# STML451RE_Buck_HSE.net
KiCad netlist of a schematic drawn in EAGLE
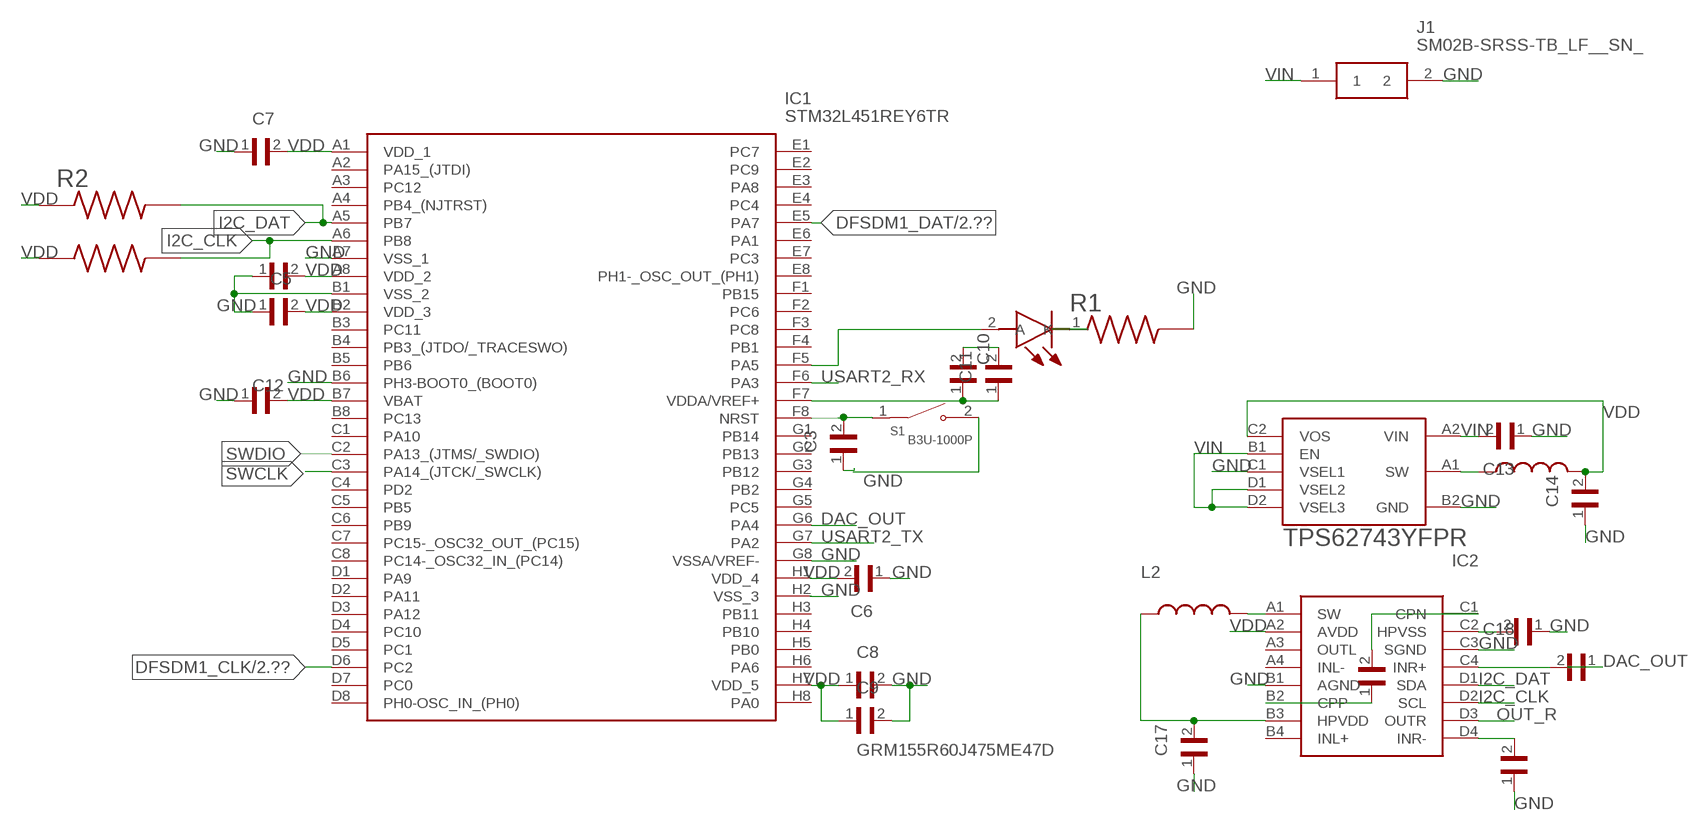
[diagram p0: schematic, sheet 1]
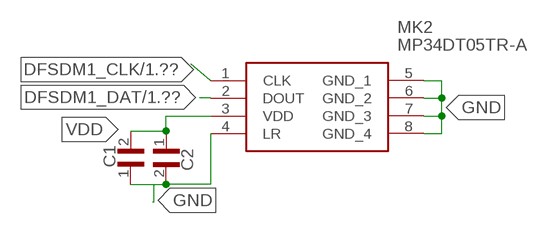
[diagram p1: schematic, sheet 2]

(export (version "E")
  (design (tool "Eeschema 10.0.6"))
  (components
    (comp (ref "C3")
      (value "GRM033C80J104KE15D")
      (footprint "eagle-import:CAPC0603X33N")
      (fields (field (name "DIGI-KEY_PART_NUMBER") "490-10390-1-ND") (field (name "MF") "Murata Electronics"))
      (libsource (lib "eagle-import") (part "GRM033C80J104KE15D"))
    )
    (comp (ref "C4")
      (value "GRM033C80J104KE15D")
      (footprint "eagle-import:CAPC0603X33N")
      (fields (field (name "DIGI-KEY_PART_NUMBER") "490-10390-1-ND") (field (name "MF") "Murata Electronics"))
      (libsource (lib "eagle-import") (part "GRM033C80J104KE15D"))
    )
    (comp (ref "C5")
      (value "GRM033C80J104KE15D")
      (footprint "eagle-import:CAPC0603X33N")
      (fields (field (name "DIGI-KEY_PART_NUMBER") "490-10390-1-ND") (field (name "MF") "Murata Electronics"))
      (libsource (lib "eagle-import") (part "GRM033C80J104KE15D"))
    )
    (comp (ref "C6")
      (value "GRM033C80J104KE15D")
      (footprint "eagle-import:CAPC0603X33N")
      (fields (field (name "DIGI-KEY_PART_NUMBER") "490-10390-1-ND") (field (name "MF") "Murata Electronics"))
      (libsource (lib "eagle-import") (part "GRM033C80J104KE15D"))
    )
    (comp (ref "C7")
      (value "GRM033C80J104KE15D")
      (footprint "eagle-import:CAPC0603X33N")
      (fields (field (name "DIGI-KEY_PART_NUMBER") "490-10390-1-ND") (field (name "MF") "Murata Electronics"))
      (libsource (lib "eagle-import") (part "GRM033C80J104KE15D"))
    )
    (comp (ref "C8")
      (value "GRM033C80J104KE15D")
      (footprint "eagle-import:CAPC0603X33N")
      (fields (field (name "DIGI-KEY_PART_NUMBER") "490-10390-1-ND") (field (name "MF") "Murata Electronics"))
      (libsource (lib "eagle-import") (part "GRM033C80J104KE15D"))
    )
    (comp (ref "C9")
      (value "GRM155R60J475ME47D")
      (footprint "eagle-import:CAPC1005X60N")
      (fields (field (name "DIGI-KEY_PART_NUMBER") "490-5915-1-ND") (field (name "MF") "Murata"))
      (libsource (lib "eagle-import") (part "GRM155R60J475ME47D"))
    )
    (comp (ref "C10")
      (value "GRM033C80J104KE15D")
      (footprint "eagle-import:CAPC0603X33N")
      (fields (field (name "DIGI-KEY_PART_NUMBER") "490-10390-1-ND") (field (name "MF") "Murata Electronics"))
      (libsource (lib "eagle-import") (part "GRM033C80J104KE15D"))
    )
    (comp (ref "C11")
      (value "JMK105C6105KV-F")
      (footprint "eagle-import:CAPC1005X55N")
      (fields (field (name "DIGI-KEY_PART_NUMBER") "587-3381-1-ND") (field (name "MF") "Taiyo Yuden"))
      (libsource (lib "eagle-import") (part "JMK105C6105KV-F"))
    )
    (comp (ref "C12")
      (value "GRM033C80J104KE15D")
      (footprint "eagle-import:CAPC0603X33N")
      (fields (field (name "DIGI-KEY_PART_NUMBER") "490-10390-1-ND") (field (name "MF") "Murata Electronics"))
      (libsource (lib "eagle-import") (part "GRM033C80J104KE15D"))
    )
    (comp (ref "C13")
      (value "GRM155R60J475ME47D")
      (footprint "eagle-import:CAPC1005X60N")
      (fields (field (name "DIGI-KEY_PART_NUMBER") "490-5915-1-ND") (field (name "MF") "Murata"))
      (libsource (lib "eagle-import") (part "GRM155R60J475ME47D"))
    )
    (comp (ref "C14")
      (value "GRM155R60J106ME15D")
      (footprint "eagle-import:CAPC1005X65N")
      (fields (field (name "DIGI-KEY_PART_NUMBER") "490-13238-1-ND") (field (name "MF") "Murata"))
      (libsource (lib "eagle-import") (part "GRM155R60J106ME15D"))
    )
    (comp (ref "C17")
      (value "GRM155R60J225KE95D")
      (footprint "eagle-import:CAPC1005X55N")
      (fields (field (name "DIGI-KEY_PART_NUMBER") "490-12532-1-ND") (field (name "MF") "Murata"))
      (libsource (lib "eagle-import") (part "GRM155R60J225KE95D"))
    )
    (comp (ref "C18")
      (value "GRM155R60J225KE95D")
      (footprint "eagle-import:CAPC1005X55N")
      (fields (field (name "DIGI-KEY_PART_NUMBER") "490-12532-1-ND") (field (name "MF") "Murata"))
      (libsource (lib "eagle-import") (part "GRM155R60J225KE95D"))
    )
    (comp (ref "C19")
      (value "JMK105C6105KV-F")
      (footprint "eagle-import:CAPC1005X55N")
      (fields (field (name "DIGI-KEY_PART_NUMBER") "587-3381-1-ND") (field (name "MF") "Taiyo Yuden"))
      (libsource (lib "eagle-import") (part "JMK105C6105KV-F"))
    )
    (comp (ref "C20")
      (value "JMK105C6105KV-F")
      (footprint "eagle-import:CAPC1005X55N")
      (fields (field (name "DIGI-KEY_PART_NUMBER") "587-3381-1-ND") (field (name "MF") "Taiyo Yuden"))
      (libsource (lib "eagle-import") (part "JMK105C6105KV-F"))
    )
    (comp (ref "C21")
      (value "JMK105C6105KV-F")
      (footprint "eagle-import:CAPC1005X55N")
      (fields (field (name "DIGI-KEY_PART_NUMBER") "587-3381-1-ND") (field (name "MF") "Taiyo Yuden"))
      (libsource (lib "eagle-import") (part "JMK105C6105KV-F"))
    )
    (comp (ref "IC1")
      (value "STM32L451REY6TR")
      (footprint "eagle-import:BGA64C40P8X8_336X366X58")
      (fields (field (name "MOUSER_PART_NUMBER") "511-STM32L451REY6TR"))
      (libsource (lib "eagle-import") (part "STM32L451REY6TR"))
    )
    (comp (ref "IC2")
      (value "TPA6140A2YFFT")
      (footprint "eagle-import:BGA16C40P4X4_156X156X63")
      (fields (field (name "MOUSER_PART_NUMBER") "595-TPA6140A2YFFT"))
      (libsource (lib "eagle-import") (part "TPA6140A2YFFT"))
    )
    (comp (ref "J1")
      (value "SM02B-SRSS-TB_LF__SN_")
      (footprint "eagle-import:SM02B-SRSS-TB")
      (fields (field (name "ARROW_PART_NUMBER") "SM02B-SRSS-TB(LF)(SN)"))
      (libsource (lib "eagle-import") (part "SM02B-SRSS-TB_LF__SN_"))
    )
    (comp (ref "L1")
      (value "1285AS-H-2R2M=P2")
      (footprint "eagle-import:INDC2016X100N")
      (fields (field (name "DIGI-KEY_PART_NUMBER") "490-10600-1-ND") (field (name "MF") "Murata Electronics"))
      (libsource (lib "eagle-import") (part "1285AS-H-2R2M=P2"))
    )
    (comp (ref "L2")
      (value "LQM21PN2R2MC0D")
      (footprint "eagle-import:INDC2012X55N")
      (fields (field (name "DIGI-KEY_PART_NUMBER") "490-4994-1-ND") (field (name "MF") "Murata"))
      (libsource (lib "eagle-import") (part "LQM21PN2R2MC0D"))
    )
    (comp (ref "LED1")
      (value "VLMS1500-GS08")
      (footprint "eagle-import:VLMG1500GS08")
      (fields (field (name "MOUSER_PART_NUMBER") "78-VLMS1500-GS08"))
      (libsource (lib "eagle-import") (part "VLMS1500-GS08"))
    )
    (comp (ref "R1")
      (value "CRCW02012K20FKED")
      (footprint "eagle-import:RESC0603X28N")
      (fields (field (name "DIGI-KEY_PART_NUMBER") "541-2.20KAABCT-ND") (field (name "MF") "Vishay"))
      (libsource (lib "eagle-import") (part "CRCW02012K20FKED"))
    )
    (comp (ref "R2")
      (value "ERA-2AEB122X")
      (footprint "eagle-import:RESC1005X40N")
      (fields (field (name "DIGI-KEY_PART_NUMBER") "P1.2KDCCT-ND") (field (name "MF") "Panasonic"))
      (libsource (lib "eagle-import") (part "ERA-2AEB122X"))
    )
    (comp (ref "R3")
      (value "ERA-2AEB122X")
      (footprint "eagle-import:RESC1005X40N")
      (fields (field (name "DIGI-KEY_PART_NUMBER") "P1.2KDCCT-ND") (field (name "MF") "Panasonic"))
      (libsource (lib "eagle-import") (part "ERA-2AEB122X"))
    )
    (comp (ref "S1")
      (value "B3U-1000P")
      (footprint "eagle-import:SW_B3U-1000P")
      (fields (field (name "DIGI-KEY_PART_NUMBER") "SW1020CT-ND") (field (name "MF") "Omron"))
      (libsource (lib "eagle-import") (part "B3U-1000P"))
    )
    (comp (ref "U1")
      (value "TPS62743YFPR")
      (footprint "eagle-import:BGA8N40P2X4_87X156X50")
      (fields (field (name "DIGI-KEY_PART_NUMBER") "296-42392-1-ND") (field (name "MF") "Texas Instruments"))
      (libsource (lib "eagle-import") (part "TPS62743YFPR"))
    )
    (comp (ref "C1")
      (value "GRM033C80J104KE15D")
      (footprint "eagle-import:CAPC0603X33N")
      (fields (field (name "DIGI-KEY_PART_NUMBER") "490-10390-1-ND") (field (name "MF") "Murata Electronics"))
      (libsource (lib "eagle-import") (part "GRM033C80J104KE15D"))
    )
    (comp (ref "C2")
      (value "JMK105C6105KV-F")
      (footprint "eagle-import:CAPC1005X55N")
      (fields (field (name "DIGI-KEY_PART_NUMBER") "587-3381-1-ND") (field (name "MF") "Taiyo Yuden"))
      (libsource (lib "eagle-import") (part "JMK105C6105KV-F"))
    )
    (comp (ref "MK2")
      (value "MP34DT05TR-A")
      (footprint "eagle-import:MP34DT05TRA")
      (fields (field (name "MOUSER_PART_NUMBER") "511-MP34DT05TR-A"))
      (libsource (lib "eagle-import") (part "MP34DT05TR-A"))
    )
  )
  (nets
    (net (code "1") (name "DAC_OUT") (class "Default")
      (node (ref "C21") (pin "1") (pinfunction "1_1") (pintype "passive"))
      (node (ref "IC1") (pin "G6") (pinfunction "PA4_G6") (pintype "bidirectional"))
    )
    (net (code "2") (name "DFSDM1_CLK") (class "Default")
      (node (ref "IC1") (pin "D6") (pinfunction "PC2_D6") (pintype "bidirectional"))
      (node (ref "MK2") (pin "1") (pinfunction "CLK_1") (pintype "bidirectional"))
    )
    (net (code "3") (name "DFSDM1_DAT") (class "Default")
      (node (ref "IC1") (pin "E5") (pinfunction "PA7_E5") (pintype "bidirectional"))
      (node (ref "MK2") (pin "2") (pinfunction "DOUT_2") (pintype "bidirectional"))
    )
    (net (code "4") (name "GND") (class "Default")
      (node (ref "C12") (pin "1") (pinfunction "1_1") (pintype "passive"))
      (node (ref "C13") (pin "1") (pinfunction "1_1") (pintype "passive"))
      (node (ref "C14") (pin "1") (pinfunction "1_1") (pintype "passive"))
      (node (ref "C17") (pin "1") (pinfunction "1_1") (pintype "passive"))
      (node (ref "C18") (pin "1") (pinfunction "1_1") (pintype "passive"))
      (node (ref "C20") (pin "1") (pinfunction "1_1") (pintype "passive"))
      (node (ref "C3") (pin "1") (pinfunction "1_1") (pintype "passive"))
      (node (ref "C4") (pin "1") (pinfunction "1_1") (pintype "passive"))
      (node (ref "C5") (pin "1") (pinfunction "1_1") (pintype "passive"))
      (node (ref "C6") (pin "1") (pinfunction "1_1") (pintype "passive"))
      (node (ref "C7") (pin "1") (pinfunction "1_1") (pintype "passive"))
      (node (ref "C8") (pin "2") (pinfunction "2_2") (pintype "passive"))
      (node (ref "C9") (pin "2") (pinfunction "2_2") (pintype "passive"))
      (node (ref "IC1") (pin "A7") (pinfunction "VSS_1_A7") (pintype "bidirectional"))
      (node (ref "IC1") (pin "B1") (pinfunction "VSS_2_B1") (pintype "bidirectional"))
      (node (ref "IC1") (pin "B6") (pinfunction "PH3-BOOT0_(BOOT0)_B6") (pintype "bidirectional"))
      (node (ref "IC1") (pin "G8") (pinfunction "VSSA/VREF-_G8") (pintype "bidirectional"))
      (node (ref "IC1") (pin "H2") (pinfunction "VSS_3_H2") (pintype "bidirectional"))
      (node (ref "IC2") (pin "B1") (pinfunction "AGND_B1") (pintype "bidirectional"))
      (node (ref "IC2") (pin "C3") (pinfunction "SGND_C3") (pintype "bidirectional"))
      (node (ref "J1") (pin "2") (pinfunction "2_2") (pintype "bidirectional"))
      (node (ref "MK2") (pin "5") (pinfunction "GND_1_5") (pintype "bidirectional"))
      (node (ref "MK2") (pin "6") (pinfunction "GND_2_6") (pintype "bidirectional"))
      (node (ref "MK2") (pin "7") (pinfunction "GND_3_7") (pintype "bidirectional"))
      (node (ref "MK2") (pin "8") (pinfunction "GND_4_8") (pintype "bidirectional"))
      (node (ref "R1") (pin "2") (pinfunction "2_2") (pintype "passive"))
      (node (ref "U1") (pin "B2") (pinfunction "GND_B2") (pintype "passive"))
      (node (ref "U1") (pin "C1") (pinfunction "VSEL1_C1") (pintype "input"))
    )
    (net (code "5") (name "I2C_CLK") (class "Default")
      (node (ref "IC1") (pin "A6") (pinfunction "PB8_A6") (pintype "bidirectional"))
      (node (ref "IC2") (pin "D2") (pinfunction "SCL_D2") (pintype "bidirectional"))
      (node (ref "R3") (pin "2") (pinfunction "2_2") (pintype "passive"))
    )
    (net (code "6") (name "I2C_DAT") (class "Default")
      (node (ref "IC1") (pin "A5") (pinfunction "PB7_A5") (pintype "bidirectional"))
      (node (ref "IC2") (pin "D1") (pinfunction "SDA_D1") (pintype "bidirectional"))
      (node (ref "R2") (pin "2") (pinfunction "2_2") (pintype "passive"))
    )
    (net (code "7") (name "Net-(C3-Pad2)") (class "Default")
      (node (ref "C3") (pin "2") (pinfunction "2_2") (pintype "passive"))
      (node (ref "S1") (pin "1") (pinfunction "1_1") (pintype "passive"))
    )
    (net (code "8") (name "Net-(C10-Pad2)") (class "Default")
      (node (ref "C10") (pin "2") (pinfunction "2_2") (pintype "passive"))
      (node (ref "C11") (pin "2") (pinfunction "2_2") (pintype "passive"))
    )
    (net (code "9") (name "Net-(IC1-PA5)") (class "Default")
      (node (ref "IC1") (pin "F5") (pinfunction "PA5_F5") (pintype "bidirectional"))
      (node (ref "LED1") (pin "2") (pinfunction "A_2") (pintype "bidirectional"))
    )
    (net (code "10") (name "Net-(IC1-VDDA{slash}VREF+)") (class "Default")
      (node (ref "C10") (pin "1") (pinfunction "1_1") (pintype "passive"))
      (node (ref "C11") (pin "1") (pinfunction "1_1") (pintype "passive"))
      (node (ref "IC1") (pin "F7") (pinfunction "VDDA/VREF+_F7") (pintype "bidirectional"))
    )
    (net (code "11") (name "Net-(IC2-CPN)") (class "Default")
      (node (ref "C19") (pin "2") (pinfunction "2_2") (pintype "passive"))
      (node (ref "IC2") (pin "C1") (pinfunction "CPN_C1") (pintype "bidirectional"))
    )
    (net (code "12") (name "Net-(IC2-CPP)") (class "Default")
      (node (ref "C19") (pin "1") (pinfunction "1_1") (pintype "passive"))
      (node (ref "IC2") (pin "B2") (pinfunction "CPP_B2") (pintype "bidirectional"))
    )
    (net (code "13") (name "Net-(IC2-HPVDD)") (class "Default")
      (node (ref "C17") (pin "2") (pinfunction "2_2") (pintype "passive"))
      (node (ref "IC2") (pin "B3") (pinfunction "HPVDD_B3") (pintype "bidirectional"))
      (node (ref "L2") (pin "1") (pinfunction "1_1") (pintype "passive"))
    )
    (net (code "14") (name "Net-(IC2-HPVSS)") (class "Default")
      (node (ref "C18") (pin "2") (pinfunction "2_2") (pintype "passive"))
      (node (ref "IC2") (pin "C2") (pinfunction "HPVSS_C2") (pintype "bidirectional"))
    )
    (net (code "15") (name "Net-(IC2-INR+)") (class "Default")
      (node (ref "C21") (pin "2") (pinfunction "2_2") (pintype "passive"))
      (node (ref "IC2") (pin "C4") (pinfunction "INR+_C4") (pintype "bidirectional"))
    )
    (net (code "16") (name "Net-(IC2-INR-)") (class "Default")
      (node (ref "C20") (pin "2") (pinfunction "2_2") (pintype "passive"))
      (node (ref "IC2") (pin "D4") (pinfunction "INR-_D4") (pintype "bidirectional"))
    )
    (net (code "17") (name "Net-(IC2-SW)") (class "Default")
      (node (ref "IC2") (pin "A1") (pinfunction "SW_A1") (pintype "bidirectional"))
      (node (ref "L2") (pin "2") (pinfunction "2_2") (pintype "passive"))
    )
    (net (code "18") (name "Net-(LED1-K)") (class "Default")
      (node (ref "LED1") (pin "1") (pinfunction "K_1") (pintype "bidirectional"))
      (node (ref "R1") (pin "1") (pinfunction "1_1") (pintype "passive"))
    )
    (net (code "19") (name "Net-(MK2-LR)") (class "Default")
      (node (ref "C1") (pin "1") (pinfunction "1_1") (pintype "passive"))
      (node (ref "C2") (pin "2") (pinfunction "2_2") (pintype "passive"))
      (node (ref "MK2") (pin "4") (pinfunction "LR_4") (pintype "bidirectional"))
    )
    (net (code "20") (name "Net-(U1-SW)") (class "Default")
      (node (ref "L1") (pin "1") (pinfunction "1_1") (pintype "passive"))
      (node (ref "U1") (pin "A1") (pinfunction "SW_A1") (pintype "output"))
    )
    (net (code "21") (name "OUT_R") (class "Default")
      (node (ref "IC2") (pin "D3") (pinfunction "OUTR_D3") (pintype "bidirectional"))
    )
    (net (code "22") (name "SWCLK") (class "Default")
      (node (ref "IC1") (pin "C3") (pinfunction "PA14_(JTCK/_SWCLK)_C3") (pintype "bidirectional"))
    )
    (net (code "23") (name "SWDIO") (class "Default")
      (node (ref "IC1") (pin "C2") (pinfunction "PA13_(JTMS/_SWDIO)_C2") (pintype "bidirectional"))
    )
    (net (code "24") (name "USART2_RX") (class "Default")
      (node (ref "IC1") (pin "F6") (pinfunction "PA3_F6") (pintype "bidirectional"))
    )
    (net (code "25") (name "USART2_TX") (class "Default")
      (node (ref "IC1") (pin "G7") (pinfunction "PA2_G7") (pintype "bidirectional"))
    )
    (net (code "26") (name "VDD") (class "Default")
      (node (ref "C1") (pin "2") (pinfunction "2_2") (pintype "passive"))
      (node (ref "C12") (pin "2") (pinfunction "2_2") (pintype "passive"))
      (node (ref "C14") (pin "2") (pinfunction "2_2") (pintype "passive"))
      (node (ref "C2") (pin "1") (pinfunction "1_1") (pintype "passive"))
      (node (ref "C4") (pin "2") (pinfunction "2_2") (pintype "passive"))
      (node (ref "C5") (pin "2") (pinfunction "2_2") (pintype "passive"))
      (node (ref "C6") (pin "2") (pinfunction "2_2") (pintype "passive"))
      (node (ref "C7") (pin "2") (pinfunction "2_2") (pintype "passive"))
      (node (ref "C8") (pin "1") (pinfunction "1_1") (pintype "passive"))
      (node (ref "C9") (pin "1") (pinfunction "1_1") (pintype "passive"))
      (node (ref "IC1") (pin "A1") (pinfunction "VDD_1_A1") (pintype "bidirectional"))
      (node (ref "IC1") (pin "A8") (pinfunction "VDD_2_A8") (pintype "bidirectional"))
      (node (ref "IC1") (pin "B2") (pinfunction "VDD_3_B2") (pintype "bidirectional"))
      (node (ref "IC1") (pin "B7") (pinfunction "VBAT_B7") (pintype "bidirectional"))
      (node (ref "IC1") (pin "H1") (pinfunction "VDD_4_H1") (pintype "bidirectional"))
      (node (ref "IC1") (pin "H7") (pinfunction "VDD_5_H7") (pintype "bidirectional"))
      (node (ref "IC2") (pin "A2") (pinfunction "AVDD_A2") (pintype "bidirectional"))
      (node (ref "L1") (pin "2") (pinfunction "2_2") (pintype "passive"))
      (node (ref "MK2") (pin "3") (pinfunction "VDD_3") (pintype "bidirectional"))
      (node (ref "R2") (pin "1") (pinfunction "1_1") (pintype "passive"))
      (node (ref "R3") (pin "1") (pinfunction "1_1") (pintype "passive"))
      (node (ref "U1") (pin "C2") (pinfunction "VOS_C2") (pintype "input"))
    )
    (net (code "27") (name "VIN") (class "Default")
      (node (ref "C13") (pin "2") (pinfunction "2_2") (pintype "passive"))
      (node (ref "J1") (pin "1") (pinfunction "1_1") (pintype "bidirectional"))
      (node (ref "U1") (pin "A2") (pinfunction "VIN_A2") (pintype "power_in"))
      (node (ref "U1") (pin "B1") (pinfunction "EN_B1") (pintype "input"))
      (node (ref "U1") (pin "D1") (pinfunction "VSEL2_D1") (pintype "input"))
      (node (ref "U1") (pin "D2") (pinfunction "VSEL3_D2") (pintype "input"))
    )
    (net (code "28") (name "unconnected-(IC1-NRST-PadF8)") (class "Default")
      (node (ref "IC1") (pin "F8") (pinfunction "NRST_F8") (pintype "bidirectional"))
    )
    (net (code "29") (name "unconnected-(IC1-PA0-PadH8)") (class "Default")
      (node (ref "IC1") (pin "H8") (pinfunction "PA0_H8") (pintype "bidirectional"))
    )
    (net (code "30") (name "unconnected-(IC1-PA1-PadE6)") (class "Default")
      (node (ref "IC1") (pin "E6") (pinfunction "PA1_E6") (pintype "bidirectional"))
    )
    (net (code "31") (name "unconnected-(IC1-PA6-PadH6)") (class "Default")
      (node (ref "IC1") (pin "H6") (pinfunction "PA6_H6") (pintype "bidirectional"))
    )
    (net (code "32") (name "unconnected-(IC1-PA8-PadE3)") (class "Default")
      (node (ref "IC1") (pin "E3") (pinfunction "PA8_E3") (pintype "bidirectional"))
    )
    (net (code "33") (name "unconnected-(IC1-PA9-PadD1)") (class "Default")
      (node (ref "IC1") (pin "D1") (pinfunction "PA9_D1") (pintype "bidirectional"))
    )
    (net (code "34") (name "unconnected-(IC1-PA10-PadC1)") (class "Default")
      (node (ref "IC1") (pin "C1") (pinfunction "PA10_C1") (pintype "bidirectional"))
    )
    (net (code "35") (name "unconnected-(IC1-PA11-PadD2)") (class "Default")
      (node (ref "IC1") (pin "D2") (pinfunction "PA11_D2") (pintype "bidirectional"))
    )
    (net (code "36") (name "unconnected-(IC1-PA12-PadD3)") (class "Default")
      (node (ref "IC1") (pin "D3") (pinfunction "PA12_D3") (pintype "bidirectional"))
    )
    (net (code "37") (name "unconnected-(IC1-PA15_(JTDI)-PadA2)") (class "Default")
      (node (ref "IC1") (pin "A2") (pinfunction "PA15_(JTDI)_A2") (pintype "bidirectional"))
    )
    (net (code "38") (name "unconnected-(IC1-PB0-PadH5)") (class "Default")
      (node (ref "IC1") (pin "H5") (pinfunction "PB0_H5") (pintype "bidirectional"))
    )
    (net (code "39") (name "unconnected-(IC1-PB1-PadF4)") (class "Default")
      (node (ref "IC1") (pin "F4") (pinfunction "PB1_F4") (pintype "bidirectional"))
    )
    (net (code "40") (name "unconnected-(IC1-PB2-PadG4)") (class "Default")
      (node (ref "IC1") (pin "G4") (pinfunction "PB2_G4") (pintype "bidirectional"))
    )
    (net (code "41") (name "unconnected-(IC1-PB3_(JTDO{slash}_TRACESWO)-PadB4)") (class "Default")
      (node (ref "IC1") (pin "B4") (pinfunction "PB3_(JTDO/_TRACESWO)_B4") (pintype "bidirectional"))
    )
    (net (code "42") (name "unconnected-(IC1-PB4_(NJTRST)-PadA4)") (class "Default")
      (node (ref "IC1") (pin "A4") (pinfunction "PB4_(NJTRST)_A4") (pintype "bidirectional"))
    )
    (net (code "43") (name "unconnected-(IC1-PB5-PadC5)") (class "Default")
      (node (ref "IC1") (pin "C5") (pinfunction "PB5_C5") (pintype "bidirectional"))
    )
    (net (code "44") (name "unconnected-(IC1-PB6-PadB5)") (class "Default")
      (node (ref "IC1") (pin "B5") (pinfunction "PB6_B5") (pintype "bidirectional"))
    )
    (net (code "45") (name "unconnected-(IC1-PB9-PadC6)") (class "Default")
      (node (ref "IC1") (pin "C6") (pinfunction "PB9_C6") (pintype "bidirectional"))
    )
    (net (code "46") (name "unconnected-(IC1-PB10-PadH4)") (class "Default")
      (node (ref "IC1") (pin "H4") (pinfunction "PB10_H4") (pintype "bidirectional"))
    )
    (net (code "47") (name "unconnected-(IC1-PB11-PadH3)") (class "Default")
      (node (ref "IC1") (pin "H3") (pinfunction "PB11_H3") (pintype "bidirectional"))
    )
    (net (code "48") (name "unconnected-(IC1-PB12-PadG3)") (class "Default")
      (node (ref "IC1") (pin "G3") (pinfunction "PB12_G3") (pintype "bidirectional"))
    )
    (net (code "49") (name "unconnected-(IC1-PB13-PadG2)") (class "Default")
      (node (ref "IC1") (pin "G2") (pinfunction "PB13_G2") (pintype "bidirectional"))
    )
    (net (code "50") (name "unconnected-(IC1-PB14-PadG1)") (class "Default")
      (node (ref "IC1") (pin "G1") (pinfunction "PB14_G1") (pintype "bidirectional"))
    )
    (net (code "51") (name "unconnected-(IC1-PB15-PadF1)") (class "Default")
      (node (ref "IC1") (pin "F1") (pinfunction "PB15_F1") (pintype "bidirectional"))
    )
    (net (code "52") (name "unconnected-(IC1-PC0-PadD7)") (class "Default")
      (node (ref "IC1") (pin "D7") (pinfunction "PC0_D7") (pintype "bidirectional"))
    )
    (net (code "53") (name "unconnected-(IC1-PC1-PadD5)") (class "Default")
      (node (ref "IC1") (pin "D5") (pinfunction "PC1_D5") (pintype "bidirectional"))
    )
    (net (code "54") (name "unconnected-(IC1-PC3-PadE7)") (class "Default")
      (node (ref "IC1") (pin "E7") (pinfunction "PC3_E7") (pintype "bidirectional"))
    )
    (net (code "55") (name "unconnected-(IC1-PC4-PadE4)") (class "Default")
      (node (ref "IC1") (pin "E4") (pinfunction "PC4_E4") (pintype "bidirectional"))
    )
    (net (code "56") (name "unconnected-(IC1-PC5-PadG5)") (class "Default")
      (node (ref "IC1") (pin "G5") (pinfunction "PC5_G5") (pintype "bidirectional"))
    )
    (net (code "57") (name "unconnected-(IC1-PC6-PadF2)") (class "Default")
      (node (ref "IC1") (pin "F2") (pinfunction "PC6_F2") (pintype "bidirectional"))
    )
    (net (code "58") (name "unconnected-(IC1-PC7-PadE1)") (class "Default")
      (node (ref "IC1") (pin "E1") (pinfunction "PC7_E1") (pintype "bidirectional"))
    )
    (net (code "59") (name "unconnected-(IC1-PC8-PadF3)") (class "Default")
      (node (ref "IC1") (pin "F3") (pinfunction "PC8_F3") (pintype "bidirectional"))
    )
    (net (code "60") (name "unconnected-(IC1-PC9-PadE2)") (class "Default")
      (node (ref "IC1") (pin "E2") (pinfunction "PC9_E2") (pintype "bidirectional"))
    )
    (net (code "61") (name "unconnected-(IC1-PC10-PadD4)") (class "Default")
      (node (ref "IC1") (pin "D4") (pinfunction "PC10_D4") (pintype "bidirectional"))
    )
    (net (code "62") (name "unconnected-(IC1-PC11-PadB3)") (class "Default")
      (node (ref "IC1") (pin "B3") (pinfunction "PC11_B3") (pintype "bidirectional"))
    )
    (net (code "63") (name "unconnected-(IC1-PC12-PadA3)") (class "Default")
      (node (ref "IC1") (pin "A3") (pinfunction "PC12_A3") (pintype "bidirectional"))
    )
    (net (code "64") (name "unconnected-(IC1-PC13-PadB8)") (class "Default")
      (node (ref "IC1") (pin "B8") (pinfunction "PC13_B8") (pintype "bidirectional"))
    )
    (net (code "65") (name "unconnected-(IC1-PC14-_OSC32_IN_(PC14)-PadC8)") (class "Default")
      (node (ref "IC1") (pin "C8") (pinfunction "PC14-_OSC32_IN_(PC14)_C8") (pintype "bidirectional"))
    )
    (net (code "66") (name "unconnected-(IC1-PC15-_OSC32_OUT_(PC15)-PadC7)") (class "Default")
      (node (ref "IC1") (pin "C7") (pinfunction "PC15-_OSC32_OUT_(PC15)_C7") (pintype "bidirectional"))
    )
    (net (code "67") (name "unconnected-(IC1-PD2-PadC4)") (class "Default")
      (node (ref "IC1") (pin "C4") (pinfunction "PD2_C4") (pintype "bidirectional"))
    )
    (net (code "68") (name "unconnected-(IC1-PH0-OSC_IN_(PH0)-PadD8)") (class "Default")
      (node (ref "IC1") (pin "D8") (pinfunction "PH0-OSC_IN_(PH0)_D8") (pintype "bidirectional"))
    )
    (net (code "69") (name "unconnected-(IC1-PH1-_OSC_OUT_(PH1)-PadE8)") (class "Default")
      (node (ref "IC1") (pin "E8") (pinfunction "PH1-_OSC_OUT_(PH1)_E8") (pintype "bidirectional"))
    )
    (net (code "70") (name "unconnected-(IC2-INL+-PadB4)") (class "Default")
      (node (ref "IC2") (pin "B4") (pinfunction "INL+_B4") (pintype "bidirectional"))
    )
    (net (code "71") (name "unconnected-(IC2-INL--PadA4)") (class "Default")
      (node (ref "IC2") (pin "A4") (pinfunction "INL-_A4") (pintype "bidirectional"))
    )
    (net (code "72") (name "unconnected-(IC2-OUTL-PadA3)") (class "Default")
      (node (ref "IC2") (pin "A3") (pinfunction "OUTL_A3") (pintype "bidirectional"))
    )
    (net (code "73") (name "unconnected-(S1-Pad2)") (class "Default")
      (node (ref "S1") (pin "2") (pinfunction "2_2") (pintype "passive"))
    )
  )
)
